# 7x6keyboard_untested.net
KiCad netlist of a schematic drawn in EAGLE
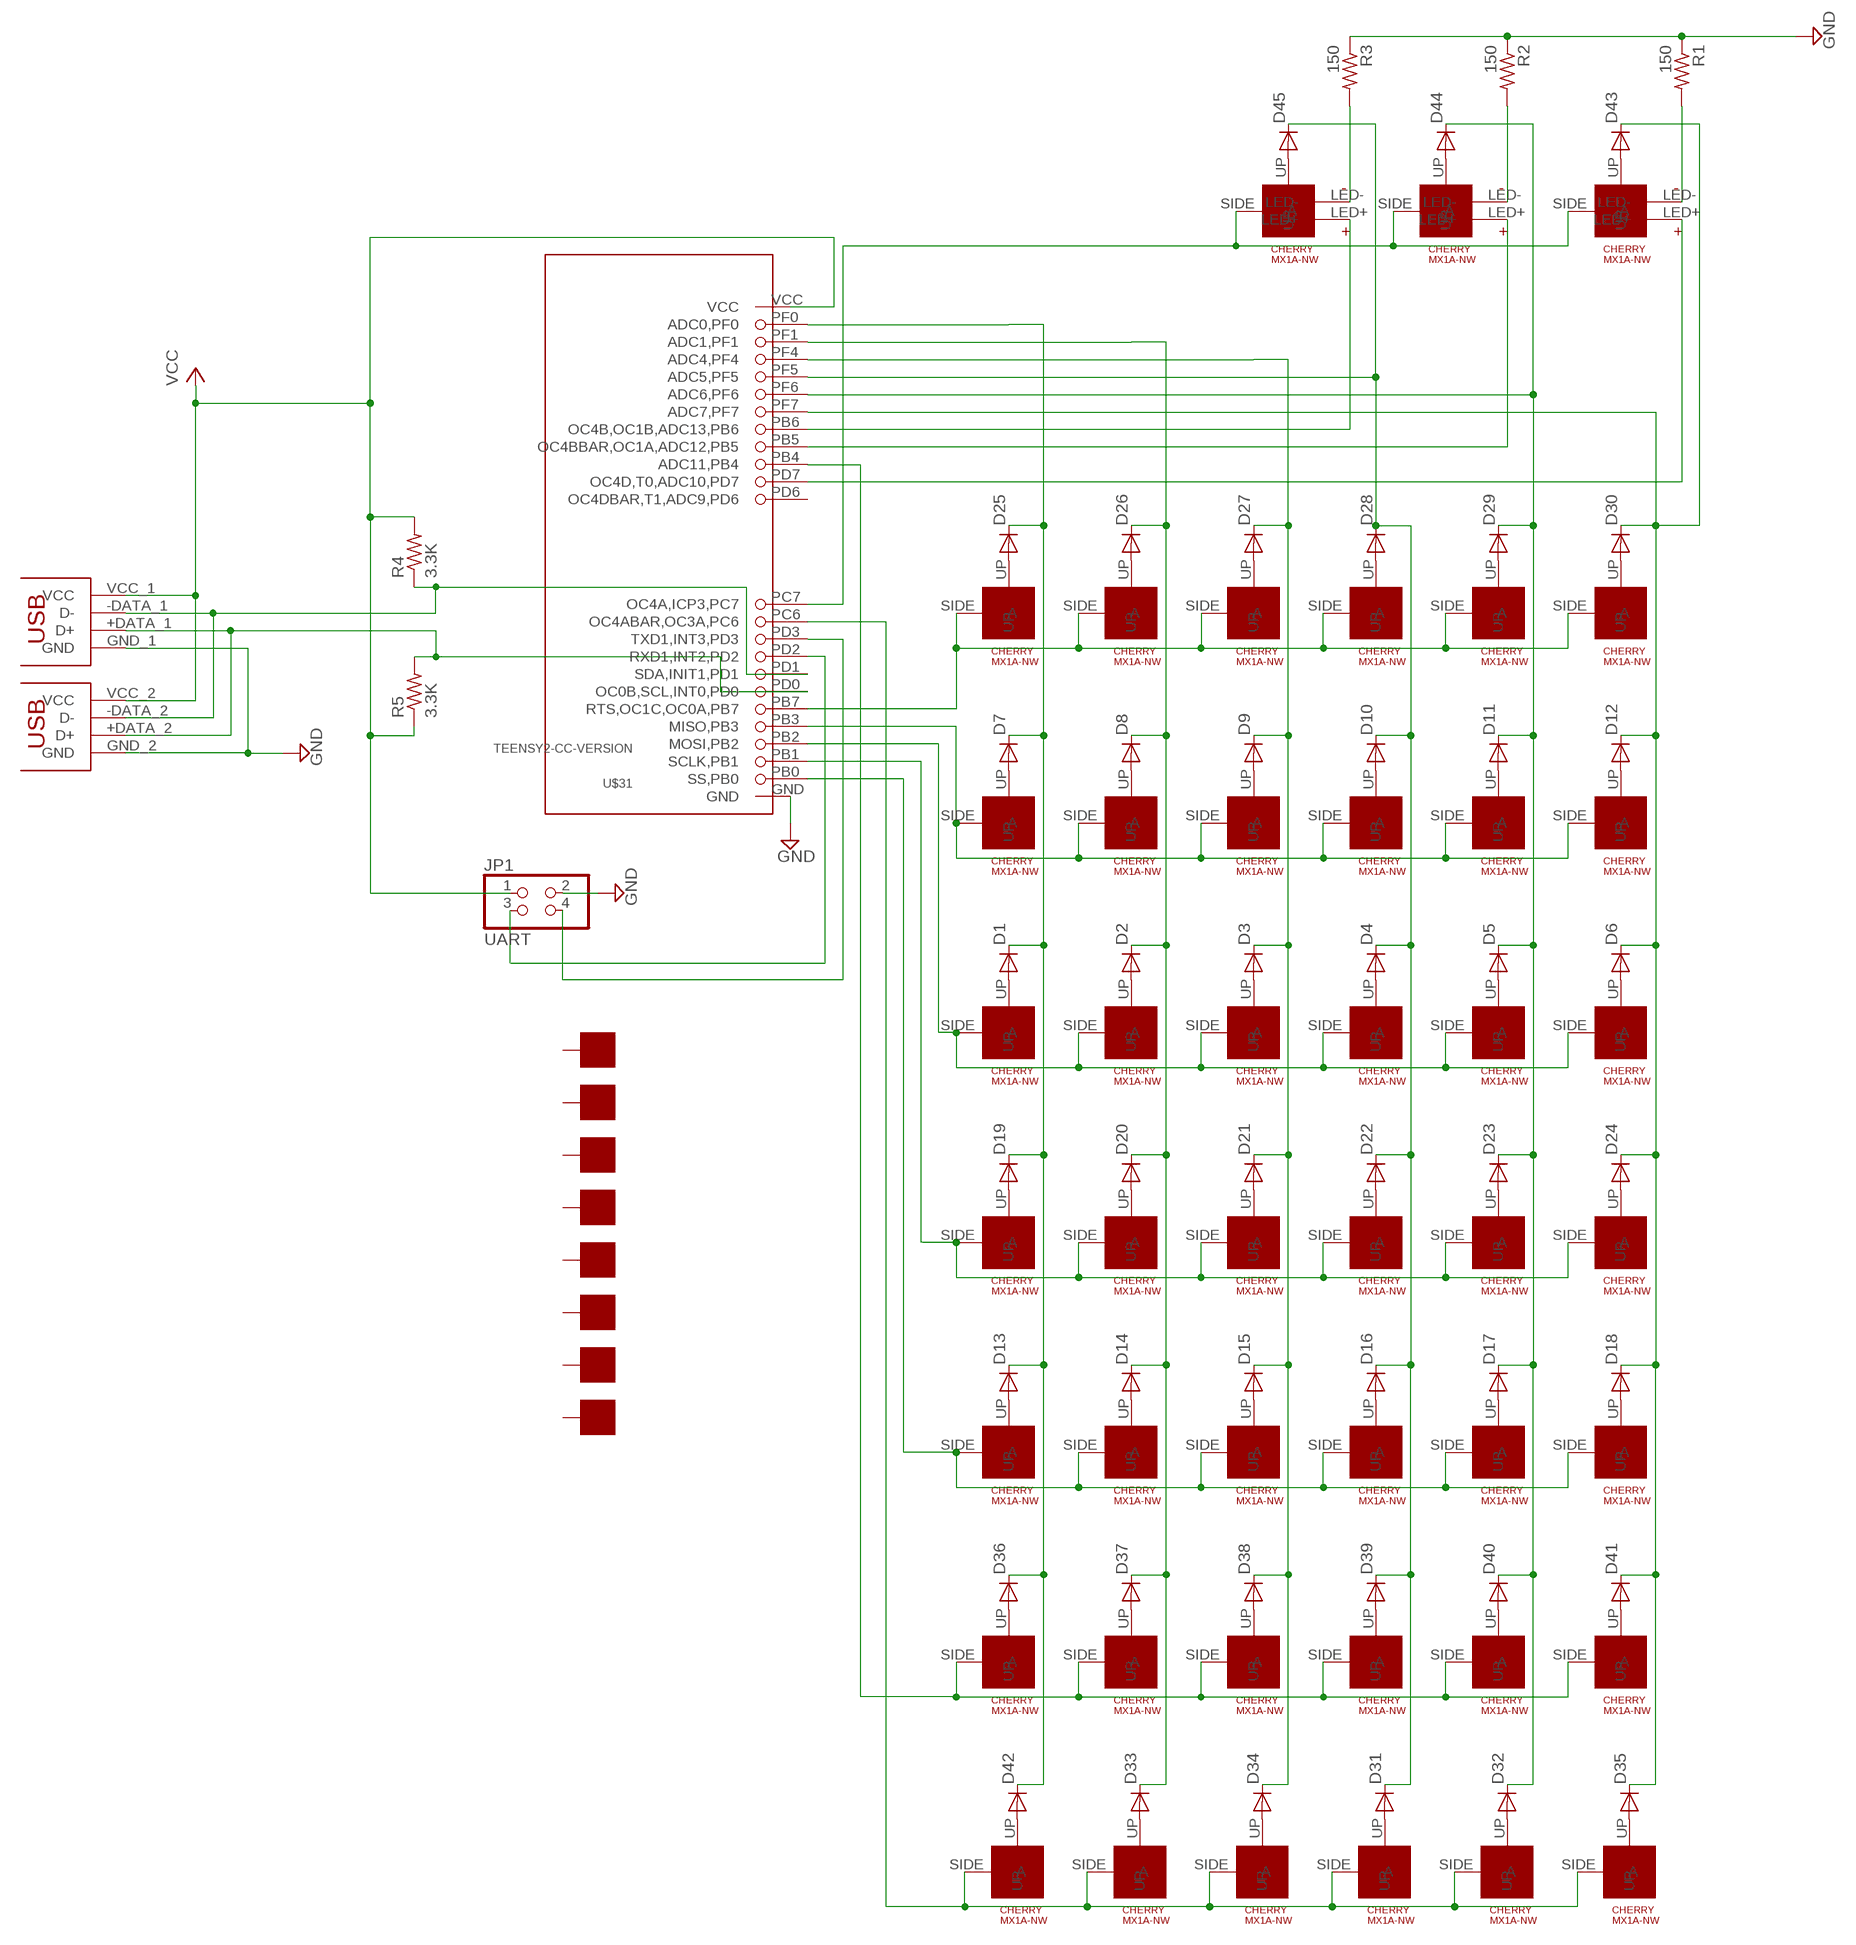
[diagram p0: schematic, sheet 1]

(export (version "E")
  (design (tool "Eeschema 10.0.6"))
  (components
    (comp (ref "D1")
      (value "1N4148DO35-7")
      (footprint "eagle-import:DO35-7")
      (libsource (lib "eagle-import") (part "1N4148DO35-7"))
    )
    (comp (ref "D2")
      (value "1N4148DO35-7")
      (footprint "eagle-import:DO35-7")
      (libsource (lib "eagle-import") (part "1N4148DO35-7"))
    )
    (comp (ref "D3")
      (value "1N4148DO35-7")
      (footprint "eagle-import:DO35-7")
      (libsource (lib "eagle-import") (part "1N4148DO35-7"))
    )
    (comp (ref "D4")
      (value "1N4148DO35-7")
      (footprint "eagle-import:DO35-7")
      (libsource (lib "eagle-import") (part "1N4148DO35-7"))
    )
    (comp (ref "D5")
      (value "1N4148DO35-7")
      (footprint "eagle-import:DO35-7")
      (libsource (lib "eagle-import") (part "1N4148DO35-7"))
    )
    (comp (ref "D6")
      (value "1N4148DO35-7")
      (footprint "eagle-import:DO35-7")
      (libsource (lib "eagle-import") (part "1N4148DO35-7"))
    )
    (comp (ref "D7")
      (value "1N4148DO35-7")
      (footprint "eagle-import:DO35-7")
      (libsource (lib "eagle-import") (part "1N4148DO35-7"))
    )
    (comp (ref "D8")
      (value "1N4148DO35-7")
      (footprint "eagle-import:DO35-7")
      (libsource (lib "eagle-import") (part "1N4148DO35-7"))
    )
    (comp (ref "D9")
      (value "1N4148DO35-7")
      (footprint "eagle-import:DO35-7")
      (libsource (lib "eagle-import") (part "1N4148DO35-7"))
    )
    (comp (ref "D10")
      (value "1N4148DO35-7")
      (footprint "eagle-import:DO35-7")
      (libsource (lib "eagle-import") (part "1N4148DO35-7"))
    )
    (comp (ref "D11")
      (value "1N4148DO35-7")
      (footprint "eagle-import:DO35-7")
      (libsource (lib "eagle-import") (part "1N4148DO35-7"))
    )
    (comp (ref "D12")
      (value "1N4148DO35-7")
      (footprint "eagle-import:DO35-7")
      (libsource (lib "eagle-import") (part "1N4148DO35-7"))
    )
    (comp (ref "D13")
      (value "1N4148DO35-7")
      (footprint "eagle-import:DO35-7")
      (libsource (lib "eagle-import") (part "1N4148DO35-7"))
    )
    (comp (ref "D14")
      (value "1N4148DO35-7")
      (footprint "eagle-import:DO35-7")
      (libsource (lib "eagle-import") (part "1N4148DO35-7"))
    )
    (comp (ref "D15")
      (value "1N4148DO35-7")
      (footprint "eagle-import:DO35-7")
      (libsource (lib "eagle-import") (part "1N4148DO35-7"))
    )
    (comp (ref "D16")
      (value "1N4148DO35-7")
      (footprint "eagle-import:DO35-7")
      (libsource (lib "eagle-import") (part "1N4148DO35-7"))
    )
    (comp (ref "D17")
      (value "1N4148DO35-7")
      (footprint "eagle-import:DO35-7")
      (libsource (lib "eagle-import") (part "1N4148DO35-7"))
    )
    (comp (ref "D18")
      (value "1N4148DO35-7")
      (footprint "eagle-import:DO35-7")
      (libsource (lib "eagle-import") (part "1N4148DO35-7"))
    )
    (comp (ref "D19")
      (value "1N4148DO35-7")
      (footprint "eagle-import:DO35-7")
      (libsource (lib "eagle-import") (part "1N4148DO35-7"))
    )
    (comp (ref "D20")
      (value "1N4148DO35-7")
      (footprint "eagle-import:DO35-7")
      (libsource (lib "eagle-import") (part "1N4148DO35-7"))
    )
    (comp (ref "D21")
      (value "1N4148DO35-7")
      (footprint "eagle-import:DO35-7")
      (libsource (lib "eagle-import") (part "1N4148DO35-7"))
    )
    (comp (ref "D22")
      (value "1N4148DO35-7")
      (footprint "eagle-import:DO35-7")
      (libsource (lib "eagle-import") (part "1N4148DO35-7"))
    )
    (comp (ref "D23")
      (value "1N4148DO35-7")
      (footprint "eagle-import:DO35-7")
      (libsource (lib "eagle-import") (part "1N4148DO35-7"))
    )
    (comp (ref "D24")
      (value "1N4148DO35-7")
      (footprint "eagle-import:DO35-7")
      (libsource (lib "eagle-import") (part "1N4148DO35-7"))
    )
    (comp (ref "D25")
      (value "1N4148DO35-7")
      (footprint "eagle-import:DO35-7")
      (libsource (lib "eagle-import") (part "1N4148DO35-7"))
    )
    (comp (ref "D26")
      (value "1N4148DO35-7")
      (footprint "eagle-import:DO35-7")
      (libsource (lib "eagle-import") (part "1N4148DO35-7"))
    )
    (comp (ref "D27")
      (value "1N4148DO35-7")
      (footprint "eagle-import:DO35-7")
      (libsource (lib "eagle-import") (part "1N4148DO35-7"))
    )
    (comp (ref "D28")
      (value "1N4148DO35-7")
      (footprint "eagle-import:DO35-7")
      (libsource (lib "eagle-import") (part "1N4148DO35-7"))
    )
    (comp (ref "D29")
      (value "1N4148DO35-7")
      (footprint "eagle-import:DO35-7")
      (libsource (lib "eagle-import") (part "1N4148DO35-7"))
    )
    (comp (ref "D30")
      (value "1N4148DO35-7")
      (footprint "eagle-import:DO35-7")
      (libsource (lib "eagle-import") (part "1N4148DO35-7"))
    )
    (comp (ref "D31")
      (value "1N4148DO35-7")
      (footprint "eagle-import:DO35-7")
      (libsource (lib "eagle-import") (part "1N4148DO35-7"))
    )
    (comp (ref "D32")
      (value "1N4148DO35-7")
      (footprint "eagle-import:DO35-7")
      (libsource (lib "eagle-import") (part "1N4148DO35-7"))
    )
    (comp (ref "D33")
      (value "1N4148DO35-7")
      (footprint "eagle-import:DO35-7")
      (libsource (lib "eagle-import") (part "1N4148DO35-7"))
    )
    (comp (ref "D34")
      (value "1N4148DO35-7")
      (footprint "eagle-import:DO35-7")
      (libsource (lib "eagle-import") (part "1N4148DO35-7"))
    )
    (comp (ref "D35")
      (value "1N4148DO35-7")
      (footprint "eagle-import:DO35-7")
      (libsource (lib "eagle-import") (part "1N4148DO35-7"))
    )
    (comp (ref "D36")
      (value "1N4148DO35-7")
      (footprint "eagle-import:DO35-7")
      (libsource (lib "eagle-import") (part "1N4148DO35-7"))
    )
    (comp (ref "D37")
      (value "1N4148DO35-7")
      (footprint "eagle-import:DO35-7")
      (libsource (lib "eagle-import") (part "1N4148DO35-7"))
    )
    (comp (ref "D38")
      (value "1N4148DO35-7")
      (footprint "eagle-import:DO35-7")
      (libsource (lib "eagle-import") (part "1N4148DO35-7"))
    )
    (comp (ref "D39")
      (value "1N4148DO35-7")
      (footprint "eagle-import:DO35-7")
      (libsource (lib "eagle-import") (part "1N4148DO35-7"))
    )
    (comp (ref "D40")
      (value "1N4148DO35-7")
      (footprint "eagle-import:DO35-7")
      (libsource (lib "eagle-import") (part "1N4148DO35-7"))
    )
    (comp (ref "D41")
      (value "1N4148DO35-7")
      (footprint "eagle-import:DO35-7")
      (libsource (lib "eagle-import") (part "1N4148DO35-7"))
    )
    (comp (ref "D42")
      (value "1N4148DO35-7")
      (footprint "eagle-import:DO35-7")
      (libsource (lib "eagle-import") (part "1N4148DO35-7"))
    )
    (comp (ref "D43")
      (value "1N4148DO35-7")
      (footprint "eagle-import:DO35-7")
      (libsource (lib "eagle-import") (part "1N4148DO35-7"))
    )
    (comp (ref "D44")
      (value "1N4148DO35-7")
      (footprint "eagle-import:DO35-7")
      (libsource (lib "eagle-import") (part "1N4148DO35-7"))
    )
    (comp (ref "D45")
      (value "1N4148DO35-7")
      (footprint "eagle-import:DO35-7")
      (libsource (lib "eagle-import") (part "1N4148DO35-7"))
    )
    (comp (ref "JP1")
      (value "UART")
      (footprint "eagle-import:2X02")
      (libsource (lib "eagle-import") (part "PINHD-2X2"))
    )
    (comp (ref "R1")
      (value "150")
      (footprint "eagle-import:0207_10")
      (libsource (lib "eagle-import") (part "R-US_0207/10"))
    )
    (comp (ref "R2")
      (value "150")
      (footprint "eagle-import:0207_10")
      (libsource (lib "eagle-import") (part "R-US_0207/10"))
    )
    (comp (ref "R3")
      (value "150")
      (footprint "eagle-import:0207_10")
      (libsource (lib "eagle-import") (part "R-US_0207/10"))
    )
    (comp (ref "R4")
      (value "3.3K")
      (footprint "eagle-import:0207_10")
      (libsource (lib "eagle-import") (part "resistor_R-US_0207/10"))
    )
    (comp (ref "R5")
      (value "3.3K")
      (footprint "eagle-import:0207_10")
      (libsource (lib "eagle-import") (part "resistor_R-US_0207/10"))
    )
    (comp (ref "U$1")
      (value "CHERRY-MX1A-E1NW")
      (footprint "eagle-import:CHERRYMX-NN")
      (libsource (lib "eagle-import") (part "CHERRY-MX1A-E1NW"))
    )
    (comp (ref "U$2")
      (value "CHERRY-MX1A-E1NW")
      (footprint "eagle-import:CHERRYMX-NN")
      (libsource (lib "eagle-import") (part "CHERRY-MX1A-E1NW"))
    )
    (comp (ref "U$3")
      (value "CHERRY-MX1A-E1NW")
      (footprint "eagle-import:CHERRYMX-NN")
      (libsource (lib "eagle-import") (part "CHERRY-MX1A-E1NW"))
    )
    (comp (ref "U$4")
      (value "CHERRY-MX1A-E1NW")
      (footprint "eagle-import:CHERRYMX-NN")
      (libsource (lib "eagle-import") (part "CHERRY-MX1A-E1NW"))
    )
    (comp (ref "U$5")
      (value "CHERRY-MX1A-E1NW")
      (footprint "eagle-import:CHERRYMX-NN")
      (libsource (lib "eagle-import") (part "CHERRY-MX1A-E1NW"))
    )
    (comp (ref "U$6")
      (value "CHERRY-MX1A-E1NW")
      (footprint "eagle-import:CHERRYMX-NN")
      (libsource (lib "eagle-import") (part "CHERRY-MX1A-E1NW"))
    )
    (comp (ref "U$7")
      (value "CHERRY-MX1A-E1NW")
      (footprint "eagle-import:CHERRYMX-NN")
      (libsource (lib "eagle-import") (part "CHERRY-MX1A-E1NW"))
    )
    (comp (ref "U$8")
      (value "CHERRY-MX1A-E1NW")
      (footprint "eagle-import:CHERRYMX-NN")
      (libsource (lib "eagle-import") (part "CHERRY-MX1A-E1NW"))
    )
    (comp (ref "U$9")
      (value "CHERRY-MX1A-E1NW")
      (footprint "eagle-import:CHERRYMX-NN")
      (libsource (lib "eagle-import") (part "CHERRY-MX1A-E1NW"))
    )
    (comp (ref "U$10")
      (value "CHERRY-MX1A-E1NW")
      (footprint "eagle-import:CHERRYMX-NN")
      (libsource (lib "eagle-import") (part "CHERRY-MX1A-E1NW"))
    )
    (comp (ref "U$11")
      (value "CHERRY-MX1A-E1NW")
      (footprint "eagle-import:CHERRYMX-NN")
      (libsource (lib "eagle-import") (part "CHERRY-MX1A-E1NW"))
    )
    (comp (ref "U$12")
      (value "CHERRY-MX1A-E1NW")
      (footprint "eagle-import:CHERRYMX-NN")
      (libsource (lib "eagle-import") (part "CHERRY-MX1A-E1NW"))
    )
    (comp (ref "U$13")
      (value "CHERRY-MX1A-E1NW")
      (footprint "eagle-import:CHERRYMX-NN")
      (libsource (lib "eagle-import") (part "CHERRY-MX1A-E1NW"))
    )
    (comp (ref "U$14")
      (value "CHERRY-MX1A-E1NW")
      (footprint "eagle-import:CHERRYMX-NN")
      (libsource (lib "eagle-import") (part "CHERRY-MX1A-E1NW"))
    )
    (comp (ref "U$15")
      (value "CHERRY-MX1A-E1NW")
      (footprint "eagle-import:CHERRYMX-NN")
      (libsource (lib "eagle-import") (part "CHERRY-MX1A-E1NW"))
    )
    (comp (ref "U$16")
      (value "CHERRY-MX1A-E1NW")
      (footprint "eagle-import:CHERRYMX-NN")
      (libsource (lib "eagle-import") (part "CHERRY-MX1A-E1NW"))
    )
    (comp (ref "U$17")
      (value "CHERRY-MX1A-E1NW")
      (footprint "eagle-import:CHERRYMX-NN")
      (libsource (lib "eagle-import") (part "CHERRY-MX1A-E1NW"))
    )
    (comp (ref "U$18")
      (value "CHERRY-MX1A-E1NW")
      (footprint "eagle-import:CHERRYMX-NN")
      (libsource (lib "eagle-import") (part "CHERRY-MX1A-E1NW"))
    )
    (comp (ref "U$19")
      (value "CHERRY-MX1A-E1NW")
      (footprint "eagle-import:CHERRYMX-NN")
      (libsource (lib "eagle-import") (part "CHERRY-MX1A-E1NW"))
    )
    (comp (ref "U$20")
      (value "CHERRY-MX1A-E1NW")
      (footprint "eagle-import:CHERRYMX-NN")
      (libsource (lib "eagle-import") (part "CHERRY-MX1A-E1NW"))
    )
    (comp (ref "U$21")
      (value "CHERRY-MX1A-E1NW")
      (footprint "eagle-import:CHERRYMX-NN")
      (libsource (lib "eagle-import") (part "CHERRY-MX1A-E1NW"))
    )
    (comp (ref "U$22")
      (value "CHERRY-MX1A-E1NW")
      (footprint "eagle-import:CHERRYMX-NN")
      (libsource (lib "eagle-import") (part "CHERRY-MX1A-E1NW"))
    )
    (comp (ref "U$23")
      (value "CHERRY-MX1A-E1NW")
      (footprint "eagle-import:CHERRYMX-NN")
      (libsource (lib "eagle-import") (part "CHERRY-MX1A-E1NW"))
    )
    (comp (ref "U$24")
      (value "CHERRY-MX1A-E1NW")
      (footprint "eagle-import:CHERRYMX-NN")
      (libsource (lib "eagle-import") (part "CHERRY-MX1A-E1NW"))
    )
    (comp (ref "U$25")
      (value "CHERRY-MX1A-E1NW")
      (footprint "eagle-import:CHERRYMX-NN")
      (libsource (lib "eagle-import") (part "CHERRY-MX1A-E1NW"))
    )
    (comp (ref "U$26")
      (value "CHERRY-MX1A-E1NW")
      (footprint "eagle-import:CHERRYMX-NN")
      (libsource (lib "eagle-import") (part "CHERRY-MX1A-E1NW"))
    )
    (comp (ref "U$27")
      (value "CHERRY-MX1A-E1NW")
      (footprint "eagle-import:CHERRYMX-NN")
      (libsource (lib "eagle-import") (part "CHERRY-MX1A-E1NW"))
    )
    (comp (ref "U$28")
      (value "CHERRY-MX1A-E1NW")
      (footprint "eagle-import:CHERRYMX-NN")
      (libsource (lib "eagle-import") (part "CHERRY-MX1A-E1NW"))
    )
    (comp (ref "U$29")
      (value "CHERRY-MX1A-E1NW")
      (footprint "eagle-import:CHERRYMX-NN")
      (libsource (lib "eagle-import") (part "CHERRY-MX1A-E1NW"))
    )
    (comp (ref "U$30")
      (value "CHERRY-MX1A-E1NW")
      (footprint "eagle-import:CHERRYMX-NN")
      (libsource (lib "eagle-import") (part "CHERRY-MX1A-E1NW"))
    )
    (comp (ref "U$31")
      (value "TEENSY2-CC-VERSION")
      (footprint "eagle-import:TEENSY2")
      (libsource (lib "eagle-import") (part "TEENSY2-CC-VERSION"))
    )
    (comp (ref "U$32")
      (value "CHERRY-MX1A-E1NW-LED")
      (footprint "eagle-import:CHERRYMX-NN-LED")
      (libsource (lib "eagle-import") (part "CHERRY-MX1A-E1NW-LED"))
    )
    (comp (ref "U$33")
      (value "CHERRY-MX1A-E1NW-LED")
      (footprint "eagle-import:CHERRYMX-NN-LED")
      (libsource (lib "eagle-import") (part "CHERRY-MX1A-E1NW-LED"))
    )
    (comp (ref "U$34")
      (value "CHERRY-MX1A-E1NW-LED")
      (footprint "eagle-import:CHERRYMX-NN-LED")
      (libsource (lib "eagle-import") (part "CHERRY-MX1A-E1NW-LED"))
    )
    (comp (ref "U$35")
      (value "DUAL-USB-A")
      (footprint "eagle-import:DUAL-USB-A")
      (libsource (lib "eagle-import") (part "DUAL-USB-A"))
    )
    (comp (ref "U$36")
      (value "CHERRY-MX1A-E1NW")
      (footprint "eagle-import:CHERRYMX-NN")
      (libsource (lib "eagle-import") (part "CHERRY-MX1A-E1NW"))
    )
    (comp (ref "U$37")
      (value "CHERRY-MX1A-E1NW")
      (footprint "eagle-import:CHERRYMX-NN")
      (libsource (lib "eagle-import") (part "CHERRY-MX1A-E1NW"))
    )
    (comp (ref "U$38")
      (value "CHERRY-MX1A-E1NW")
      (footprint "eagle-import:CHERRYMX-NN")
      (libsource (lib "eagle-import") (part "CHERRY-MX1A-E1NW"))
    )
    (comp (ref "U$39")
      (value "CHERRY-MX1A-E1NW")
      (footprint "eagle-import:CHERRYMX-NN")
      (libsource (lib "eagle-import") (part "CHERRY-MX1A-E1NW"))
    )
    (comp (ref "U$40")
      (value "CHERRY-MX1A-E1NW")
      (footprint "eagle-import:CHERRYMX-NN")
      (libsource (lib "eagle-import") (part "CHERRY-MX1A-E1NW"))
    )
    (comp (ref "U$41")
      (value "CHERRY-MX1A-E1NW")
      (footprint "eagle-import:CHERRYMX-NN")
      (libsource (lib "eagle-import") (part "CHERRY-MX1A-E1NW"))
    )
    (comp (ref "U$42")
      (value "CHERRY-MX1A-E1NW")
      (footprint "eagle-import:CHERRYMX-NN")
      (libsource (lib "eagle-import") (part "CHERRY-MX1A-E1NW"))
    )
    (comp (ref "U$43")
      (value "CHERRY-MX1A-E1NW")
      (footprint "eagle-import:CHERRYMX-NN")
      (libsource (lib "eagle-import") (part "CHERRY-MX1A-E1NW"))
    )
    (comp (ref "U$44")
      (value "CHERRY-MX1A-E1NW")
      (footprint "eagle-import:CHERRYMX-NN")
      (libsource (lib "eagle-import") (part "CHERRY-MX1A-E1NW"))
    )
    (comp (ref "U$45")
      (value "CHERRY-MX1A-E1NW")
      (footprint "eagle-import:CHERRYMX-NN")
      (libsource (lib "eagle-import") (part "CHERRY-MX1A-E1NW"))
    )
    (comp (ref "U$46")
      (value "CHERRY-MX1A-E1NW")
      (footprint "eagle-import:CHERRYMX-NN")
      (libsource (lib "eagle-import") (part "CHERRY-MX1A-E1NW"))
    )
    (comp (ref "U$47")
      (value "CHERRY-MX1A-E1NW")
      (footprint "eagle-import:CHERRYMX-NN")
      (libsource (lib "eagle-import") (part "CHERRY-MX1A-E1NW"))
    )
    (comp (ref "U$48")
      (value "MOUNTING-PAD")
      (footprint "eagle-import:MOUNTING-PAD")
      (libsource (lib "eagle-import") (part "MOUNTING-PAD"))
    )
    (comp (ref "U$49")
      (value "MOUNTING-PAD")
      (footprint "eagle-import:MOUNTING-PAD")
      (libsource (lib "eagle-import") (part "MOUNTING-PAD"))
    )
    (comp (ref "U$50")
      (value "MOUNTING-PAD")
      (footprint "eagle-import:MOUNTING-PAD")
      (libsource (lib "eagle-import") (part "MOUNTING-PAD"))
    )
    (comp (ref "U$51")
      (value "MOUNTING-PAD")
      (footprint "eagle-import:MOUNTING-PAD")
      (libsource (lib "eagle-import") (part "MOUNTING-PAD"))
    )
    (comp (ref "U$52")
      (value "MOUNTING-PAD")
      (footprint "eagle-import:MOUNTING-PAD")
      (libsource (lib "eagle-import") (part "MOUNTING-PAD"))
    )
    (comp (ref "U$53")
      (value "MOUNTING-PAD")
      (footprint "eagle-import:MOUNTING-PAD")
      (libsource (lib "eagle-import") (part "MOUNTING-PAD"))
    )
    (comp (ref "U$54")
      (value "MOUNTING-PAD")
      (footprint "eagle-import:MOUNTING-PAD")
      (libsource (lib "eagle-import") (part "MOUNTING-PAD"))
    )
    (comp (ref "U$55")
      (value "MOUNTING-PAD")
      (footprint "eagle-import:MOUNTING-PAD")
      (libsource (lib "eagle-import") (part "MOUNTING-PAD"))
    )
  )
  (nets
    (net (code "1") (name "GND") (class "Default")
      (node (ref "JP1") (pin "2") (pinfunction "2_2") (pintype "passive"))
      (node (ref "R1") (pin "1") (pinfunction "1_1") (pintype "passive"))
      (node (ref "R2") (pin "1") (pinfunction "1_1") (pintype "passive"))
      (node (ref "R3") (pin "1") (pinfunction "1_1") (pintype "passive"))
      (node (ref "U$31") (pin "GND") (pinfunction "GND_GND") (pintype "power_in"))
      (node (ref "U$35") (pin "GND_1") (pinfunction "GND_GND_1") (pintype "bidirectional"))
      (node (ref "U$35") (pin "GND_2") (pinfunction "GND_GND_2") (pintype "bidirectional"))
    )
    (net (code "2") (name "Net-(D1-PadA)") (class "Default")
      (node (ref "D1") (pin "A") (pinfunction "A_A") (pintype "passive"))
      (node (ref "U$2") (pin "UP") (pinfunction "UP_UP") (pintype "bidirectional"))
    )
    (net (code "3") (name "Net-(D2-PadA)") (class "Default")
      (node (ref "D2") (pin "A") (pinfunction "A_A") (pintype "passive"))
      (node (ref "U$1") (pin "UP") (pinfunction "UP_UP") (pintype "bidirectional"))
    )
    (net (code "4") (name "Net-(D3-PadA)") (class "Default")
      (node (ref "D3") (pin "A") (pinfunction "A_A") (pintype "passive"))
      (node (ref "U$3") (pin "UP") (pinfunction "UP_UP") (pintype "bidirectional"))
    )
    (net (code "5") (name "Net-(D4-PadA)") (class "Default")
      (node (ref "D4") (pin "A") (pinfunction "A_A") (pintype "passive"))
      (node (ref "U$4") (pin "UP") (pinfunction "UP_UP") (pintype "bidirectional"))
    )
    (net (code "6") (name "Net-(D5-PadA)") (class "Default")
      (node (ref "D5") (pin "A") (pinfunction "A_A") (pintype "passive"))
      (node (ref "U$5") (pin "UP") (pinfunction "UP_UP") (pintype "bidirectional"))
    )
    (net (code "7") (name "Net-(D6-PadA)") (class "Default")
      (node (ref "D6") (pin "A") (pinfunction "A_A") (pintype "passive"))
      (node (ref "U$6") (pin "UP") (pinfunction "UP_UP") (pintype "bidirectional"))
    )
    (net (code "8") (name "Net-(D7-PadA)") (class "Default")
      (node (ref "D7") (pin "A") (pinfunction "A_A") (pintype "passive"))
      (node (ref "U$7") (pin "UP") (pinfunction "UP_UP") (pintype "bidirectional"))
    )
    (net (code "9") (name "Net-(D8-PadA)") (class "Default")
      (node (ref "D8") (pin "A") (pinfunction "A_A") (pintype "passive"))
      (node (ref "U$8") (pin "UP") (pinfunction "UP_UP") (pintype "bidirectional"))
    )
    (net (code "10") (name "Net-(D9-PadA)") (class "Default")
      (node (ref "D9") (pin "A") (pinfunction "A_A") (pintype "passive"))
      (node (ref "U$9") (pin "UP") (pinfunction "UP_UP") (pintype "bidirectional"))
    )
    (net (code "11") (name "Net-(D10-PadA)") (class "Default")
      (node (ref "D10") (pin "A") (pinfunction "A_A") (pintype "passive"))
      (node (ref "U$10") (pin "UP") (pinfunction "UP_UP") (pintype "bidirectional"))
    )
    (net (code "12") (name "Net-(D11-PadA)") (class "Default")
      (node (ref "D11") (pin "A") (pinfunction "A_A") (pintype "passive"))
      (node (ref "U$11") (pin "UP") (pinfunction "UP_UP") (pintype "bidirectional"))
    )
    (net (code "13") (name "Net-(D12-PadA)") (class "Default")
      (node (ref "D12") (pin "A") (pinfunction "A_A") (pintype "passive"))
      (node (ref "U$12") (pin "UP") (pinfunction "UP_UP") (pintype "bidirectional"))
    )
    (net (code "14") (name "Net-(D13-PadA)") (class "Default")
      (node (ref "D13") (pin "A") (pinfunction "A_A") (pintype "passive"))
      (node (ref "U$13") (pin "UP") (pinfunction "UP_UP") (pintype "bidirectional"))
    )
    (net (code "15") (name "Net-(D14-PadA)") (class "Default")
      (node (ref "D14") (pin "A") (pinfunction "A_A") (pintype "passive"))
      (node (ref "U$14") (pin "UP") (pinfunction "UP_UP") (pintype "bidirectional"))
    )
    (net (code "16") (name "Net-(D15-PadA)") (class "Default")
      (node (ref "D15") (pin "A") (pinfunction "A_A") (pintype "passive"))
      (node (ref "U$15") (pin "UP") (pinfunction "UP_UP") (pintype "bidirectional"))
    )
    (net (code "17") (name "Net-(D16-PadA)") (class "Default")
      (node (ref "D16") (pin "A") (pinfunction "A_A") (pintype "passive"))
      (node (ref "U$16") (pin "UP") (pinfunction "UP_UP") (pintype "bidirectional"))
    )
    (net (code "18") (name "Net-(D17-PadA)") (class "Default")
      (node (ref "D17") (pin "A") (pinfunction "A_A") (pintype "passive"))
      (node (ref "U$17") (pin "UP") (pinfunction "UP_UP") (pintype "bidirectional"))
    )
    (net (code "19") (name "Net-(D18-PadA)") (class "Default")
      (node (ref "D18") (pin "A") (pinfunction "A_A") (pintype "passive"))
      (node (ref "U$18") (pin "UP") (pinfunction "UP_UP") (pintype "bidirectional"))
    )
    (net (code "20") (name "Net-(D19-PadA)") (class "Default")
      (node (ref "D19") (pin "A") (pinfunction "A_A") (pintype "passive"))
      (node (ref "U$19") (pin "UP") (pinfunction "UP_UP") (pintype "bidirectional"))
    )
    (net (code "21") (name "Net-(D20-PadA)") (class "Default")
      (node (ref "D20") (pin "A") (pinfunction "A_A") (pintype "passive"))
      (node (ref "U$20") (pin "UP") (pinfunction "UP_UP") (pintype "bidirectional"))
    )
    (net (code "22") (name "Net-(D21-PadA)") (class "Default")
      (node (ref "D21") (pin "A") (pinfunction "A_A") (pintype "passive"))
      (node (ref "U$21") (pin "UP") (pinfunction "UP_UP") (pintype "bidirectional"))
    )
    (net (code "23") (name "Net-(D22-PadA)") (class "Default")
      (node (ref "D22") (pin "A") (pinfunction "A_A") (pintype "passive"))
      (node (ref "U$22") (pin "UP") (pinfunction "UP_UP") (pintype "bidirectional"))
    )
    (net (code "24") (name "Net-(D23-PadA)") (class "Default")
      (node (ref "D23") (pin "A") (pinfunction "A_A") (pintype "passive"))
      (node (ref "U$23") (pin "UP") (pinfunction "UP_UP") (pintype "bidirectional"))
    )
    (net (code "25") (name "Net-(D24-PadA)") (class "Default")
      (node (ref "D24") (pin "A") (pinfunction "A_A") (pintype "passive"))
      (node (ref "U$24") (pin "UP") (pinfunction "UP_UP") (pintype "bidirectional"))
    )
    (net (code "26") (name "Net-(D25-PadA)") (class "Default")
      (node (ref "D25") (pin "A") (pinfunction "A_A") (pintype "passive"))
      (node (ref "U$25") (pin "UP") (pinfunction "UP_UP") (pintype "bidirectional"))
    )
    (net (code "27") (name "Net-(D26-PadA)") (class "Default")
      (node (ref "D26") (pin "A") (pinfunction "A_A") (pintype "passive"))
      (node (ref "U$26") (pin "UP") (pinfunction "UP_UP") (pintype "bidirectional"))
    )
    (net (code "28") (name "Net-(D27-PadA)") (class "Default")
      (node (ref "D27") (pin "A") (pinfunction "A_A") (pintype "passive"))
      (node (ref "U$27") (pin "UP") (pinfunction "UP_UP") (pintype "bidirectional"))
    )
    (net (code "29") (name "Net-(D28-PadA)") (class "Default")
      (node (ref "D28") (pin "A") (pinfunction "A_A") (pintype "passive"))
      (node (ref "U$28") (pin "UP") (pinfunction "UP_UP") (pintype "bidirectional"))
    )
    (net (code "30") (name "Net-(D29-PadA)") (class "Default")
      (node (ref "D29") (pin "A") (pinfunction "A_A") (pintype "passive"))
      (node (ref "U$29") (pin "UP") (pinfunction "UP_UP") (pintype "bidirectional"))
    )
    (net (code "31") (name "Net-(D30-PadA)") (class "Default")
      (node (ref "D30") (pin "A") (pinfunction "A_A") (pintype "passive"))
      (node (ref "U$30") (pin "UP") (pinfunction "UP_UP") (pintype "bidirectional"))
    )
    (net (code "32") (name "Net-(D31-PadA)") (class "Default")
      (node (ref "D31") (pin "A") (pinfunction "A_A") (pintype "passive"))
      (node (ref "U$36") (pin "UP") (pinfunction "UP_UP") (pintype "bidirectional"))
    )
    (net (code "33") (name "Net-(D32-PadA)") (class "Default")
      (node (ref "D32") (pin "A") (pinfunction "A_A") (pintype "passive"))
      (node (ref "U$37") (pin "UP") (pinfunction "UP_UP") (pintype "bidirectional"))
    )
    (net (code "34") (name "Net-(D33-PadA)") (class "Default")
      (node (ref "D33") (pin "A") (pinfunction "A_A") (pintype "passive"))
      (node (ref "U$38") (pin "UP") (pinfunction "UP_UP") (pintype "bidirectional"))
    )
    (net (code "35") (name "Net-(D34-PadA)") (class "Default")
      (node (ref "D34") (pin "A") (pinfunction "A_A") (pintype "passive"))
      (node (ref "U$39") (pin "UP") (pinfunction "UP_UP") (pintype "bidirectional"))
    )
    (net (code "36") (name "Net-(D35-PadA)") (class "Default")
      (node (ref "D35") (pin "A") (pinfunction "A_A") (pintype "passive"))
      (node (ref "U$40") (pin "UP") (pinfunction "UP_UP") (pintype "bidirectional"))
    )
    (net (code "37") (name "Net-(D36-PadA)") (class "Default")
      (node (ref "D36") (pin "A") (pinfunction "A_A") (pintype "passive"))
      (node (ref "U$41") (pin "UP") (pinfunction "UP_UP") (pintype "bidirectional"))
    )
    (net (code "38") (name "Net-(D37-PadA)") (class "Default")
      (node (ref "D37") (pin "A") (pinfunction "A_A") (pintype "passive"))
      (node (ref "U$42") (pin "UP") (pinfunction "UP_UP") (pintype "bidirectional"))
    )
    (net (code "39") (name "Net-(D38-PadA)") (class "Default")
      (node (ref "D38") (pin "A") (pinfunction "A_A") (pintype "passive"))
      (node (ref "U$43") (pin "UP") (pinfunction "UP_UP") (pintype "bidirectional"))
    )
    (net (code "40") (name "Net-(D39-PadA)") (class "Default")
      (node (ref "D39") (pin "A") (pinfunction "A_A") (pintype "passive"))
      (node (ref "U$44") (pin "UP") (pinfunction "UP_UP") (pintype "bidirectional"))
    )
    (net (code "41") (name "Net-(D40-PadA)") (class "Default")
      (node (ref "D40") (pin "A") (pinfunction "A_A") (pintype "passive"))
      (node (ref "U$45") (pin "UP") (pinfunction "UP_UP") (pintype "bidirectional"))
    )
    (net (code "42") (name "Net-(D41-PadA)") (class "Default")
      (node (ref "D41") (pin "A") (pinfunction "A_A") (pintype "passive"))
      (node (ref "U$46") (pin "UP") (pinfunction "UP_UP") (pintype "bidirectional"))
    )
    (net (code "43") (name "Net-(D42-PadA)") (class "Default")
      (node (ref "D42") (pin "A") (pinfunction "A_A") (pintype "passive"))
      (node (ref "U$47") (pin "UP") (pinfunction "UP_UP") (pintype "bidirectional"))
    )
    (net (code "44") (name "Net-(D43-PadA)") (class "Default")
      (node (ref "D43") (pin "A") (pinfunction "A_A") (pintype "passive"))
      (node (ref "U$32") (pin "UP") (pinfunction "UP_UP") (pintype "bidirectional"))
    )
    (net (code "45") (name "Net-(D44-PadA)") (class "Default")
      (node (ref "D44") (pin "A") (pinfunction "A_A") (pintype "passive"))
      (node (ref "U$33") (pin "UP") (pinfunction "UP_UP") (pintype "bidirectional"))
    )
    (net (code "46") (name "Net-(D45-PadA)") (class "Default")
      (node (ref "D45") (pin "A") (pinfunction "A_A") (pintype "passive"))
      (node (ref "U$34") (pin "UP") (pinfunction "UP_UP") (pintype "bidirectional"))
    )
    (net (code "47") (name "Net-(R1-Pad2)") (class "Default")
      (node (ref "R1") (pin "2") (pinfunction "2_2") (pintype "passive"))
      (node (ref "U$32") (pin "LED-") (pinfunction "LED-_LED-") (pintype "bidirectional"))
    )
    (net (code "48") (name "Net-(R2-Pad2)") (class "Default")
      (node (ref "R2") (pin "2") (pinfunction "2_2") (pintype "passive"))
      (node (ref "U$33") (pin "LED-") (pinfunction "LED-_LED-") (pintype "bidirectional"))
    )
    (net (code "49") (name "Net-(R3-Pad2)") (class "Default")
      (node (ref "R3") (pin "2") (pinfunction "2_2") (pintype "passive"))
      (node (ref "U$34") (pin "LED-") (pinfunction "LED-_LED-") (pintype "bidirectional"))
    )
    (net (code "50") (name "Net-(U$1-A)") (class "Default")
      (node (ref "U$1") (pin "SIDE") (pinfunction "A_SIDE") (pintype "bidirectional"))
      (node (ref "U$2") (pin "SIDE") (pinfunction "A_SIDE") (pintype "bidirectional"))
      (node (ref "U$3") (pin "SIDE") (pinfunction "A_SIDE") (pintype "bidirectional"))
      (node (ref "U$31") (pin "PB2") (pinfunction "MOSI,PB2_PB2") (pintype "bidirectional"))
      (node (ref "U$4") (pin "SIDE") (pinfunction "A_SIDE") (pintype "bidirectional"))
      (node (ref "U$5") (pin "SIDE") (pinfunction "A_SIDE") (pintype "bidirectional"))
      (node (ref "U$6") (pin "SIDE") (pinfunction "A_SIDE") (pintype "bidirectional"))
    )
    (net (code "51") (name "Net-(U$10-A)") (class "Default")
      (node (ref "U$10") (pin "SIDE") (pinfunction "A_SIDE") (pintype "bidirectional"))
      (node (ref "U$11") (pin "SIDE") (pinfunction "A_SIDE") (pintype "bidirectional"))
      (node (ref "U$12") (pin "SIDE") (pinfunction "A_SIDE") (pintype "bidirectional"))
      (node (ref "U$31") (pin "PB3") (pinfunction "MISO,PB3_PB3") (pintype "bidirectional"))
      (node (ref "U$7") (pin "SIDE") (pinfunction "A_SIDE") (pintype "bidirectional"))
      (node (ref "U$8") (pin "SIDE") (pinfunction "A_SIDE") (pintype "bidirectional"))
      (node (ref "U$9") (pin "SIDE") (pinfunction "A_SIDE") (pintype "bidirectional"))
    )
    (net (code "52") (name "Net-(U$13-A)") (class "Default")
      (node (ref "U$13") (pin "SIDE") (pinfunction "A_SIDE") (pintype "bidirectional"))
      (node (ref "U$14") (pin "SIDE") (pinfunction "A_SIDE") (pintype "bidirectional"))
      (node (ref "U$15") (pin "SIDE") (pinfunction "A_SIDE") (pintype "bidirectional"))
      (node (ref "U$16") (pin "SIDE") (pinfunction "A_SIDE") (pintype "bidirectional"))
      (node (ref "U$17") (pin "SIDE") (pinfunction "A_SIDE") (pintype "bidirectional"))
      (node (ref "U$18") (pin "SIDE") (pinfunction "A_SIDE") (pintype "bidirectional"))
      (node (ref "U$31") (pin "PB0") (pinfunction "SS,PB0_PB0") (pintype "bidirectional"))
    )
    (net (code "53") (name "Net-(U$19-A)") (class "Default")
      (node (ref "U$19") (pin "SIDE") (pinfunction "A_SIDE") (pintype "bidirectional"))
      (node (ref "U$20") (pin "SIDE") (pinfunction "A_SIDE") (pintype "bidirectional"))
      (node (ref "U$21") (pin "SIDE") (pinfunction "A_SIDE") (pintype "bidirectional"))
      (node (ref "U$22") (pin "SIDE") (pinfunction "A_SIDE") (pintype "bidirectional"))
      (node (ref "U$23") (pin "SIDE") (pinfunction "A_SIDE") (pintype "bidirectional"))
      (node (ref "U$24") (pin "SIDE") (pinfunction "A_SIDE") (pintype "bidirectional"))
      (node (ref "U$31") (pin "PB1") (pinfunction "SCLK,PB1_PB1") (pintype "bidirectional"))
    )
    (net (code "54") (name "Net-(U$25-A)") (class "Default")
      (node (ref "U$25") (pin "SIDE") (pinfunction "A_SIDE") (pintype "bidirectional"))
      (node (ref "U$26") (pin "SIDE") (pinfunction "A_SIDE") (pintype "bidirectional"))
      (node (ref "U$27") (pin "SIDE") (pinfunction "A_SIDE") (pintype "bidirectional"))
      (node (ref "U$28") (pin "SIDE") (pinfunction "A_SIDE") (pintype "bidirectional"))
      (node (ref "U$29") (pin "SIDE") (pinfunction "A_SIDE") (pintype "bidirectional"))
      (node (ref "U$30") (pin "SIDE") (pinfunction "A_SIDE") (pintype "bidirectional"))
      (node (ref "U$31") (pin "PB7") (pinfunction "RTS,OC1C,OC0A,PB7_PB7") (pintype "bidirectional"))
    )
    (net (code "55") (name "Net-(U$31-ADC0,PF0)") (class "Default")
      (node (ref "D1") (pin "C") (pinfunction "C_C") (pintype "passive"))
      (node (ref "D13") (pin "C") (pinfunction "C_C") (pintype "passive"))
      (node (ref "D19") (pin "C") (pinfunction "C_C") (pintype "passive"))
      (node (ref "D25") (pin "C") (pinfunction "C_C") (pintype "passive"))
      (node (ref "D36") (pin "C") (pinfunction "C_C") (pintype "passive"))
      (node (ref "D42") (pin "C") (pinfunction "C_C") (pintype "passive"))
      (node (ref "D7") (pin "C") (pinfunction "C_C") (pintype "passive"))
      (node (ref "U$31") (pin "PF0") (pinfunction "ADC0,PF0_PF0") (pintype "bidirectional"))
    )
    (net (code "56") (name "Net-(U$31-ADC1,PF1)") (class "Default")
      (node (ref "D14") (pin "C") (pinfunction "C_C") (pintype "passive"))
      (node (ref "D2") (pin "C") (pinfunction "C_C") (pintype "passive"))
      (node (ref "D20") (pin "C") (pinfunction "C_C") (pintype "passive"))
      (node (ref "D26") (pin "C") (pinfunction "C_C") (pintype "passive"))
      (node (ref "D33") (pin "C") (pinfunction "C_C") (pintype "passive"))
      (node (ref "D37") (pin "C") (pinfunction "C_C") (pintype "passive"))
      (node (ref "D8") (pin "C") (pinfunction "C_C") (pintype "passive"))
      (node (ref "U$31") (pin "PF1") (pinfunction "ADC1,PF1_PF1") (pintype "bidirectional"))
    )
    (net (code "57") (name "Net-(U$31-ADC4,PF4)") (class "Default")
      (node (ref "D15") (pin "C") (pinfunction "C_C") (pintype "passive"))
      (node (ref "D21") (pin "C") (pinfunction "C_C") (pintype "passive"))
      (node (ref "D27") (pin "C") (pinfunction "C_C") (pintype "passive"))
      (node (ref "D3") (pin "C") (pinfunction "C_C") (pintype "passive"))
      (node (ref "D34") (pin "C") (pinfunction "C_C") (pintype "passive"))
      (node (ref "D38") (pin "C") (pinfunction "C_C") (pintype "passive"))
      (node (ref "D9") (pin "C") (pinfunction "C_C") (pintype "passive"))
      (node (ref "U$31") (pin "PF4") (pinfunction "ADC4,PF4_PF4") (pintype "bidirectional"))
    )
    (net (code "58") (name "Net-(U$31-ADC5,PF5)") (class "Default")
      (node (ref "D10") (pin "C") (pinfunction "C_C") (pintype "passive"))
      (node (ref "D16") (pin "C") (pinfunction "C_C") (pintype "passive"))
      (node (ref "D22") (pin "C") (pinfunction "C_C") (pintype "passive"))
      (node (ref "D28") (pin "C") (pinfunction "C_C") (pintype "passive"))
      (node (ref "D31") (pin "C") (pinfunction "C_C") (pintype "passive"))
      (node (ref "D39") (pin "C") (pinfunction "C_C") (pintype "passive"))
      (node (ref "D4") (pin "C") (pinfunction "C_C") (pintype "passive"))
      (node (ref "D45") (pin "C") (pinfunction "C_C") (pintype "passive"))
      (node (ref "U$31") (pin "PF5") (pinfunction "ADC5,PF5_PF5") (pintype "bidirectional"))
    )
    (net (code "59") (name "Net-(U$31-ADC6,PF6)") (class "Default")
      (node (ref "D11") (pin "C") (pinfunction "C_C") (pintype "passive"))
      (node (ref "D17") (pin "C") (pinfunction "C_C") (pintype "passive"))
      (node (ref "D23") (pin "C") (pinfunction "C_C") (pintype "passive"))
      (node (ref "D29") (pin "C") (pinfunction "C_C") (pintype "passive"))
      (node (ref "D32") (pin "C") (pinfunction "C_C") (pintype "passive"))
      (node (ref "D40") (pin "C") (pinfunction "C_C") (pintype "passive"))
      (node (ref "D44") (pin "C") (pinfunction "C_C") (pintype "passive"))
      (node (ref "D5") (pin "C") (pinfunction "C_C") (pintype "passive"))
      (node (ref "U$31") (pin "PF6") (pinfunction "ADC6,PF6_PF6") (pintype "bidirectional"))
    )
    (net (code "60") (name "Net-(U$31-ADC7,PF7)") (class "Default")
      (node (ref "D12") (pin "C") (pinfunction "C_C") (pintype "passive"))
      (node (ref "D18") (pin "C") (pinfunction "C_C") (pintype "passive"))
      (node (ref "D24") (pin "C") (pinfunction "C_C") (pintype "passive"))
      (node (ref "D30") (pin "C") (pinfunction "C_C") (pintype "passive"))
      (node (ref "D35") (pin "C") (pinfunction "C_C") (pintype "passive"))
      (node (ref "D41") (pin "C") (pinfunction "C_C") (pintype "passive"))
      (node (ref "D43") (pin "C") (pinfunction "C_C") (pintype "passive"))
      (node (ref "D6") (pin "C") (pinfunction "C_C") (pintype "passive"))
      (node (ref "U$31") (pin "PF7") (pinfunction "ADC7,PF7_PF7") (pintype "bidirectional"))
    )
    (net (code "61") (name "Net-(U$31-ADC11,PB4)") (class "Default")
      (node (ref "U$31") (pin "PB4") (pinfunction "ADC11,PB4_PB4") (pintype "bidirectional"))
      (node (ref "U$41") (pin "SIDE") (pinfunction "A_SIDE") (pintype "bidirectional"))
      (node (ref "U$42") (pin "SIDE") (pinfunction "A_SIDE") (pintype "bidirectional"))
      (node (ref "U$43") (pin "SIDE") (pinfunction "A_SIDE") (pintype "bidirectional"))
      (node (ref "U$44") (pin "SIDE") (pinfunction "A_SIDE") (pintype "bidirectional"))
      (node (ref "U$45") (pin "SIDE") (pinfunction "A_SIDE") (pintype "bidirectional"))
      (node (ref "U$46") (pin "SIDE") (pinfunction "A_SIDE") (pintype "bidirectional"))
    )
    (net (code "62") (name "Net-(U$31-OC0B,SCL,INT0,PD0)") (class "Default")
      (node (ref "R5") (pin "2") (pinfunction "2_2") (pintype "passive"))
      (node (ref "U$31") (pin "PD0") (pinfunction "OC0B,SCL,INT0,PD0_PD0") (pintype "bidirectional"))
      (node (ref "U$35") (pin "+DATA_1") (pinfunction "D+_+DATA_1") (pintype "bidirectional"))
      (node (ref "U$35") (pin "+DATA_2") (pinfunction "D+_+DATA_2") (pintype "bidirectional"))
    )
    (net (code "63") (name "Net-(U$31-OC4A,ICP3,PC7)") (class "Default")
      (node (ref "U$31") (pin "PC7") (pinfunction "OC4A,ICP3,PC7_PC7") (pintype "bidirectional"))
      (node (ref "U$32") (pin "SIDE") (pinfunction "A_SIDE") (pintype "bidirectional"))
      (node (ref "U$33") (pin "SIDE") (pinfunction "A_SIDE") (pintype "bidirectional"))
      (node (ref "U$34") (pin "SIDE") (pinfunction "A_SIDE") (pintype "bidirectional"))
    )
    (net (code "64") (name "Net-(U$31-OC4ABAR,OC3A,PC6)") (class "Default")
      (node (ref "U$31") (pin "PC6") (pinfunction "OC4ABAR,OC3A,PC6_PC6") (pintype "bidirectional"))
      (node (ref "U$36") (pin "SIDE") (pinfunction "A_SIDE") (pintype "bidirectional"))
      (node (ref "U$37") (pin "SIDE") (pinfunction "A_SIDE") (pintype "bidirectional"))
      (node (ref "U$38") (pin "SIDE") (pinfunction "A_SIDE") (pintype "bidirectional"))
      (node (ref "U$39") (pin "SIDE") (pinfunction "A_SIDE") (pintype "bidirectional"))
      (node (ref "U$40") (pin "SIDE") (pinfunction "A_SIDE") (pintype "bidirectional"))
      (node (ref "U$47") (pin "SIDE") (pinfunction "A_SIDE") (pintype "bidirectional"))
    )
    (net (code "65") (name "Net-(U$31-OC4B,OC1B,ADC13,PB6)") (class "Default")
      (node (ref "U$31") (pin "PB6") (pinfunction "OC4B,OC1B,ADC13,PB6_PB6") (pintype "bidirectional"))
      (node (ref "U$34") (pin "LED+") (pinfunction "LED+_LED+") (pintype "bidirectional"))
    )
    (net (code "66") (name "Net-(U$31-OC4BBAR,OC1A,ADC12,PB5)") (class "Default")
      (node (ref "U$31") (pin "PB5") (pinfunction "OC4BBAR,OC1A,ADC12,PB5_PB5") (pintype "bidirectional"))
      (node (ref "U$33") (pin "LED+") (pinfunction "LED+_LED+") (pintype "bidirectional"))
    )
    (net (code "67") (name "Net-(U$31-OC4D,T0,ADC10,PD7)") (class "Default")
      (node (ref "U$31") (pin "PD7") (pinfunction "OC4D,T0,ADC10,PD7_PD7") (pintype "bidirectional"))
      (node (ref "U$32") (pin "LED+") (pinfunction "LED+_LED+") (pintype "bidirectional"))
    )
    (net (code "68") (name "Net-(U$31-RXD1,INT2,PD2)") (class "Default")
      (node (ref "JP1") (pin "3") (pinfunction "3_3") (pintype "passive"))
      (node (ref "U$31") (pin "PD2") (pinfunction "RXD1,INT2,PD2_PD2") (pintype "bidirectional"))
    )
    (net (code "69") (name "Net-(U$31-SDA,INIT1,PD1)") (class "Default")
      (node (ref "R4") (pin "1") (pinfunction "1_1") (pintype "passive"))
      (node (ref "U$31") (pin "PD1") (pinfunction "SDA,INIT1,PD1_PD1") (pintype "bidirectional"))
      (node (ref "U$35") (pin "-DATA_1") (pinfunction "D-_-DATA_1") (pintype "bidirectional"))
      (node (ref "U$35") (pin "-DATA_2") (pinfunction "D-_-DATA_2") (pintype "bidirectional"))
    )
    (net (code "70") (name "Net-(U$31-TXD1,INT3,PD3)") (class "Default")
      (node (ref "JP1") (pin "4") (pinfunction "4_4") (pintype "passive"))
      (node (ref "U$31") (pin "PD3") (pinfunction "TXD1,INT3,PD3_PD3") (pintype "bidirectional"))
    )
    (net (code "71") (name "VCC") (class "Default")
      (node (ref "JP1") (pin "1") (pinfunction "1_1") (pintype "passive"))
      (node (ref "R4") (pin "2") (pinfunction "2_2") (pintype "passive"))
      (node (ref "R5") (pin "1") (pinfunction "1_1") (pintype "passive"))
      (node (ref "U$31") (pin "VCC") (pinfunction "VCC_VCC") (pintype "power_in"))
      (node (ref "U$35") (pin "VCC_1") (pinfunction "VCC_VCC_1") (pintype "bidirectional"))
      (node (ref "U$35") (pin "VCC_2") (pinfunction "VCC_VCC_2") (pintype "bidirectional"))
    )
    (net (code "72") (name "unconnected-(U$31-OC4DBAR,T1,ADC9,PD6-PadPD6)") (class "Default")
      (node (ref "U$31") (pin "PD6") (pinfunction "OC4DBAR,T1,ADC9,PD6_PD6") (pintype "bidirectional"))
    )
    (net (code "73") (name "unconnected-(U$48-PadP$1)") (class "Default")
      (node (ref "U$48") (pin "P$1") (pinfunction "P$1_P$1") (pintype "no_connect"))
    )
    (net (code "74") (name "unconnected-(U$49-PadP$1)") (class "Default")
      (node (ref "U$49") (pin "P$1") (pinfunction "P$1_P$1") (pintype "no_connect"))
    )
    (net (code "75") (name "unconnected-(U$50-PadP$1)") (class "Default")
      (node (ref "U$50") (pin "P$1") (pinfunction "P$1_P$1") (pintype "no_connect"))
    )
    (net (code "76") (name "unconnected-(U$51-PadP$1)") (class "Default")
      (node (ref "U$51") (pin "P$1") (pinfunction "P$1_P$1") (pintype "no_connect"))
    )
    (net (code "77") (name "unconnected-(U$52-PadP$1)") (class "Default")
      (node (ref "U$52") (pin "P$1") (pinfunction "P$1_P$1") (pintype "no_connect"))
    )
    (net (code "78") (name "unconnected-(U$53-PadP$1)") (class "Default")
      (node (ref "U$53") (pin "P$1") (pinfunction "P$1_P$1") (pintype "no_connect"))
    )
    (net (code "79") (name "unconnected-(U$54-PadP$1)") (class "Default")
      (node (ref "U$54") (pin "P$1") (pinfunction "P$1_P$1") (pintype "no_connect"))
    )
    (net (code "80") (name "unconnected-(U$55-PadP$1)") (class "Default")
      (node (ref "U$55") (pin "P$1") (pinfunction "P$1_P$1") (pintype "no_connect"))
    )
  )
)
